# 1_TOP.net
KiCad netlist of a schematic drawn in Altium Designer
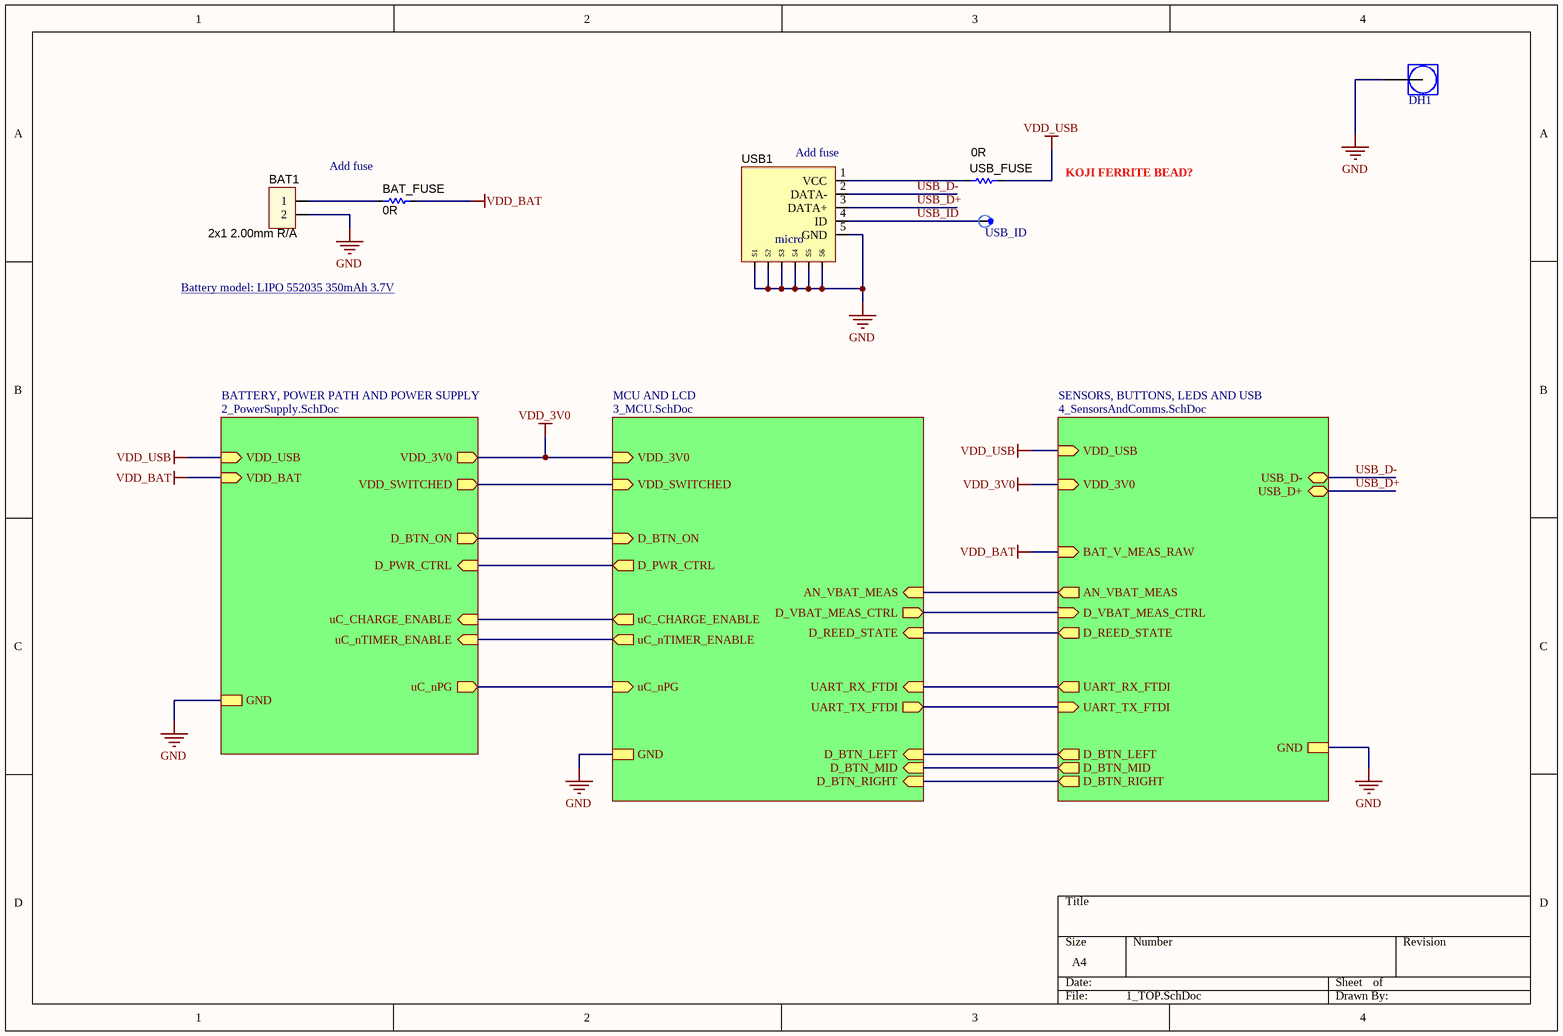
[diagram p0: 1_TOP.SchDoc]

(export (version "E")
  (design (tool "Eeschema 10.0.6"))
  (components
    (comp (ref "BAT1")
      (value "2x1 2.00mm R/A")
      (footprint "JST R/A MALE 2x2.00MM")
      (description "Connector JST-PH through-hole right angle 2.0mm pitch")
      (fields
        (field (name "MANUFACTURER") "JST Sales America Inc.")
        (field (name "MANUFACTURER PART NUMBER") "S2B-PH-K-S")
      )
      (libsource (lib "Diplomski") (part "CONN_JST_TH_R/A_2x1M_2.0mm"))
    )
    (comp (ref "BAT_FUSE")
      (value "0R")
      (footprint "RES_0603")
      (description "Resistor SMD 0603 0R 0.1W 1%")
      (fields (field (name "MANUFACTURER") "n/a") (field (name "TOLERANCE") "1%"))
      (libsource (lib "Diplomski") (part "RES_0R_1%_0.1W_0603"))
    )
    (comp (ref "DH1")
      (value "M2_Distancer_Hole_2.2mm")
      (footprint "M2 DISTANCER HOLE")
      (description "M2 Distancer hole")
      (libsource (lib "Diplomski") (part "M2_Distancer_Hole_2.2mm"))
    )
    (comp (ref "USB1")
      (value "Micro USB 5-pin")
      (footprint "MicroUSB_5POS")
      (description "Micro USB 5-pin connector")
      (fields (field (name "MANUFACTURER") "MOLEX") (field (name "MANUFACTURER PART NUMBER") "1050170001"))
      (libsource (lib "Diplomski") (part "CONN_USB-TYPEB_MICRO"))
    )
    (comp (ref "USB_FUSE")
      (value "0R")
      (footprint "RES_0603")
      (description "Resistor SMD 0603 0R 0.1W 1%")
      (fields (field (name "MANUFACTURER") "n/a") (field (name "TOLERANCE") "1%"))
      (libsource (lib "Diplomski") (part "RES_0R_1%_0.1W_0603"))
    )
    (comp (ref "USB_ID")
      (value "Testpoint_SMD")
      (footprint "Testpoint_SMD")
      (libsource (lib "Diplomski") (part "Testpoint_SMD"))
    )
  )
  (nets
    (net (code "11") (name "/USB_D+") (class "Default")
      (node (ref "USB1") (pin "3") (pinfunction "DATA+_3") (pintype "passive"))
    )
    (net (code "12") (name "/USB_D-") (class "Default")
      (node (ref "USB1") (pin "2") (pinfunction "DATA-_2") (pintype "passive"))
    )
    (net (code "13") (name "/USB_ID") (class "Default")
      (node (ref "USB1") (pin "4") (pinfunction "ID_4") (pintype "passive"))
      (node (ref "USB_ID") (pin "1") (pinfunction "1_1") (pintype "passive"))
    )
    (net (code "18") (name "GND") (class "Default")
      (node (ref "BAT1") (pin "2") (pinfunction "2_2") (pintype "passive"))
      (node (ref "DH1") (pin "1") (pinfunction "1_1") (pintype "passive"))
      (node (ref "USB1") (pin "5") (pinfunction "GND_5") (pintype "passive"))
      (node (ref "USB1") (pin "S1") (pinfunction "S1_S1") (pintype "passive"))
      (node (ref "USB1") (pin "S2") (pinfunction "S2_S2") (pintype "passive"))
      (node (ref "USB1") (pin "S3") (pinfunction "S3_S3") (pintype "passive"))
      (node (ref "USB1") (pin "S4") (pinfunction "S4_S4") (pintype "passive"))
      (node (ref "USB1") (pin "S5") (pinfunction "S5_S5") (pintype "passive"))
      (node (ref "USB1") (pin "S6") (pinfunction "S6_S6") (pintype "passive"))
    )
    (net (code "19") (name "Net-(BAT1-Pad1)") (class "Default")
      (node (ref "BAT1") (pin "1") (pinfunction "1_1") (pintype "passive"))
      (node (ref "BAT_FUSE") (pin "1") (pinfunction "1_1") (pintype "passive"))
    )
    (net (code "20") (name "Net-(USB1-VCC)") (class "Default")
      (node (ref "USB1") (pin "1") (pinfunction "VCC_1") (pintype "passive"))
      (node (ref "USB_FUSE") (pin "1") (pinfunction "1_1") (pintype "passive"))
    )
    (net (code "22") (name "VDD_BAT") (class "Default")
      (node (ref "BAT_FUSE") (pin "2") (pinfunction "2_2") (pintype "passive"))
    )
    (net (code "23") (name "VDD_USB") (class "Default")
      (node (ref "USB_FUSE") (pin "2") (pinfunction "2_2") (pintype "passive"))
    )
  )
)
